# EEPROM_I2C_AT24C512.net
KiCad netlist of a schematic drawn in Altium Designer
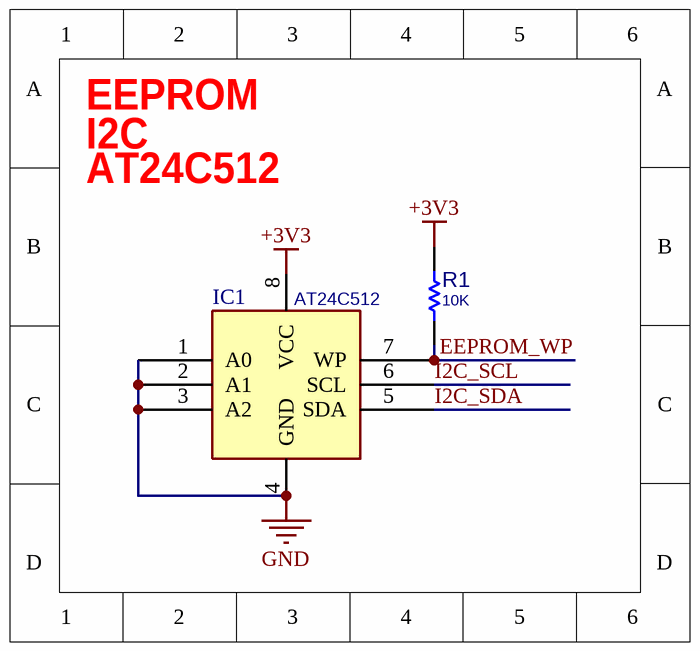
[diagram p0: EEPROM I2C AT24C512.SchDoc]

(export (version "E")
  (design (tool "Eeschema 10.0.6"))
  (components
    (comp (ref "IC1")
      (value "AT24C512")
      (footprint "SO_8")
      (description "EEPROM, I2C, 64KB")
      (libsource (lib "PW Components") (part "EEPROM_I2C_AT24C512_SOP8"))
    )
    (comp (ref "R1")
      (value "10K")
      (footprint "R0603")
      (description "RESISTOR, SMD")
      (fields (field (name "MANF_P#") "RK73H1ETTP4701F") (field (name "MANF") "KOA SPEER"))
      (libsource (lib "PW Components 97_481") (part "RES_SMD"))
    )
  )
  (nets
    (net (code "1") (name "+3V3") (class "Default")
      (node (ref "IC1") (pin "8") (pinfunction "VCC_8") (pintype "passive"))
      (node (ref "R1") (pin "2") (pinfunction "2_2") (pintype "passive"))
    )
    (net (code "2") (name "/EEPROM_WP") (class "Default")
      (node (ref "IC1") (pin "7") (pinfunction "WP_7") (pintype "passive"))
      (node (ref "R1") (pin "1") (pinfunction "1_1") (pintype "passive"))
    )
    (net (code "3") (name "/I2C_SCL") (class "Default")
      (node (ref "IC1") (pin "6") (pinfunction "SCL_6") (pintype "passive"))
    )
    (net (code "4") (name "/I2C_SDA") (class "Default")
      (node (ref "IC1") (pin "5") (pinfunction "SDA_5") (pintype "passive"))
    )
    (net (code "5") (name "GND") (class "Default")
      (node (ref "IC1") (pin "1") (pinfunction "A0_1") (pintype "passive"))
      (node (ref "IC1") (pin "2") (pinfunction "A1_2") (pintype "passive"))
      (node (ref "IC1") (pin "3") (pinfunction "A2_3") (pintype "passive"))
      (node (ref "IC1") (pin "4") (pinfunction "GND_4") (pintype "passive"))
    )
  )
)
